# PMU.net
KiCad netlist of a schematic drawn in Altium Designer
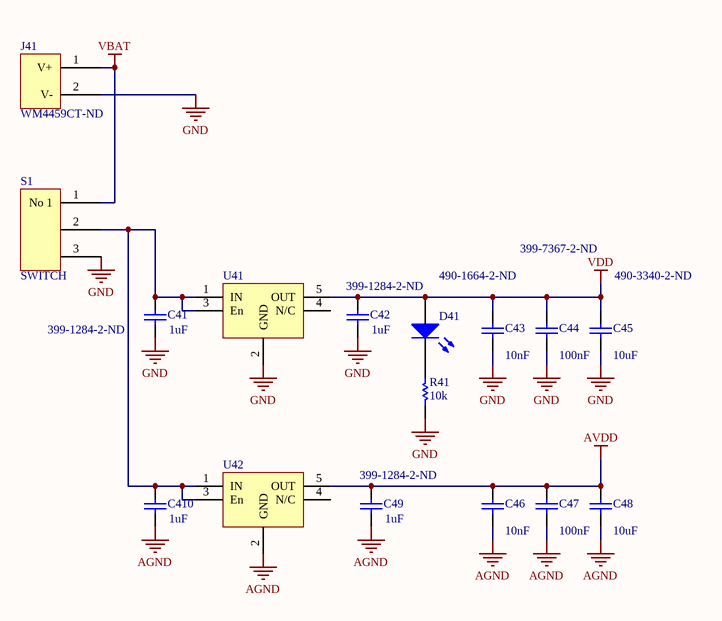
[diagram p0: PMU.SchDoc]

(export (version "E")
  (design (tool "Eeschema 10.0.6"))
  (components
    (comp (ref "C41")
      (value "1uF")
      (footprint "0402")
      (description "Capacitor (Semiconductor SIM Model)")
      (fields
        (field (name "SUPPLIER PART NUMBER 1") "399-1284-2-ND")
        (field (name "Comment") "Cap Semi")
        (field (name "PUBLISHER") "Altium Limited")
      )
      (libsource (lib "Miscellaneous Devices") (part "Cap Semi"))
    )
    (comp (ref "C42")
      (value "1uF")
      (footprint "0402")
      (description "Capacitor (Semiconductor SIM Model)")
      (fields
        (field (name "SUPPLIER PART NUMBER 1") "399-1284-2-ND")
        (field (name "Comment") "Cap Semi")
        (field (name "PUBLISHER") "Altium Limited")
      )
      (libsource (lib "Miscellaneous Devices") (part "Cap Semi"))
    )
    (comp (ref "C43")
      (value "10nF")
      (footprint "0402")
      (description "Capacitor (Semiconductor SIM Model)")
      (fields
        (field (name "SUPPLIER PART NUMBER 1") "490-1664-2-ND")
        (field (name "Comment") "Cap Semi")
        (field (name "PUBLISHER") "Altium Limited")
      )
      (libsource (lib "Miscellaneous Devices") (part "Cap Semi"))
    )
    (comp (ref "C44")
      (value "100nF")
      (footprint "0402")
      (description "Capacitor (Semiconductor SIM Model)")
      (fields
        (field (name "SUPPLIER PART NUMBER 1") "399-7367-2-ND")
        (field (name "Comment") "Cap Semi")
        (field (name "PUBLISHER") "Altium Limited")
      )
      (libsource (lib "Miscellaneous Devices") (part "Cap Semi"))
    )
    (comp (ref "C45")
      (value "10uF")
      (footprint "0402")
      (description "Capacitor (Semiconductor SIM Model)")
      (fields
        (field (name "SUPPLIER PART NUMBER 1") "490-3340-2-ND")
        (field (name "Comment") "Cap Semi")
        (field (name "PUBLISHER") "Altium Limited")
      )
      (libsource (lib "Miscellaneous Devices") (part "Cap Semi"))
    )
    (comp (ref "C46")
      (value "10nF")
      (footprint "0402")
      (description "Capacitor (Semiconductor SIM Model)")
      (fields (field (name "Comment") "Cap Semi") (field (name "PUBLISHER") "Altium Limited"))
      (libsource (lib "Miscellaneous Devices") (part "Cap Semi"))
    )
    (comp (ref "C47")
      (value "100nF")
      (footprint "0402")
      (description "Capacitor (Semiconductor SIM Model)")
      (fields (field (name "Comment") "Cap Semi") (field (name "PUBLISHER") "Altium Limited"))
      (libsource (lib "Miscellaneous Devices") (part "Cap Semi"))
    )
    (comp (ref "C48")
      (value "10uF")
      (footprint "0402")
      (description "Capacitor (Semiconductor SIM Model)")
      (fields (field (name "Comment") "Cap Semi") (field (name "PUBLISHER") "Altium Limited"))
      (libsource (lib "Miscellaneous Devices") (part "Cap Semi"))
    )
    (comp (ref "C49")
      (value "1uF")
      (footprint "0402")
      (description "Capacitor (Semiconductor SIM Model)")
      (fields
        (field (name "SUPPLIER PART NUMBER 1") "399-1284-2-ND")
        (field (name "Comment") "Cap Semi")
        (field (name "PUBLISHER") "Altium Limited")
      )
      (libsource (lib "Miscellaneous Devices") (part "Cap Semi"))
    )
    (comp (ref "C410")
      (value "1uF")
      (footprint "0402")
      (description "Capacitor (Semiconductor SIM Model)")
      (fields (field (name "Comment") "Cap Semi") (field (name "PUBLISHER") "Altium Limited"))
      (libsource (lib "Miscellaneous Devices") (part "Cap Semi"))
    )
    (comp (ref "D41")
      (value "Alim led verte")
      (footprint "0805 (2012 metric)")
      (description "LED 2X1.2MM 570NM GN WTR CLR SMD")
      (libsource (lib "Miscellaneous Devices") (part "LED3"))
    )
    (comp (ref "J41")
      (value "WM4459CT-ND")
      (footprint "WM4459CT-ND")
      (libsource (lib "WM4459CT-ND") (part "WM4459CT-ND"))
    )
    (comp (ref "R41")
      (value "10k")
      (footprint "0402")
      (description "Semiconductor Resistor")
      (fields (field (name "PUBLISHER") "Altium Limited"))
      (libsource (lib "Miscellaneous Devices") (part "Res Semi"))
    )
    (comp (ref "S1") (value "SWITCH") (footprint "CUS-12B") (libsource (lib "CUS-12B") (part "Component_1")))
    (comp (ref "U41")
      (value "Reg 3.3V")
      (footprint "TSOP-5ll")
      (description "IC REG LDO 3.3V 0.3A 5TSOP")
      (libsource (lib "EMG_library") (part "NCP603SN330T1G"))
    )
    (comp (ref "U42")
      (value "Reg 3.3V")
      (footprint "TSOP-5ll")
      (description "IC REG LDO 3.3V 0.3A 5TSOP")
      (libsource (lib "EMG_library") (part "NCP603SN330T1G"))
    )
  )
  (nets
    (net (code "1") (name "AGND") (class "Default")
      (node (ref "C410") (pin "1") (pinfunction "1_1") (pintype "passive"))
      (node (ref "C46") (pin "1") (pinfunction "1_1") (pintype "passive"))
      (node (ref "C47") (pin "1") (pinfunction "1_1") (pintype "passive"))
      (node (ref "C48") (pin "1") (pinfunction "1_1") (pintype "passive"))
      (node (ref "C49") (pin "1") (pinfunction "1_1") (pintype "passive"))
      (node (ref "U42") (pin "2") (pinfunction "GND_2") (pintype "power_in"))
    )
    (net (code "2") (name "AVDD") (class "Default")
      (node (ref "C46") (pin "2") (pinfunction "2_2") (pintype "passive"))
      (node (ref "C47") (pin "2") (pinfunction "2_2") (pintype "passive"))
      (node (ref "C48") (pin "2") (pinfunction "2_2") (pintype "passive"))
      (node (ref "C49") (pin "2") (pinfunction "2_2") (pintype "passive"))
      (node (ref "U42") (pin "5") (pinfunction "OUT_5") (pintype "power_in"))
    )
    (net (code "3") (name "GND") (class "Default")
      (node (ref "C41") (pin "1") (pinfunction "1_1") (pintype "passive"))
      (node (ref "C42") (pin "1") (pinfunction "1_1") (pintype "passive"))
      (node (ref "C43") (pin "1") (pinfunction "1_1") (pintype "passive"))
      (node (ref "C44") (pin "1") (pinfunction "1_1") (pintype "passive"))
      (node (ref "C45") (pin "1") (pinfunction "1_1") (pintype "passive"))
      (node (ref "J41") (pin "2") (pinfunction "V-_2") (pintype "passive"))
      (node (ref "R41") (pin "2") (pinfunction "2_2") (pintype "passive"))
      (node (ref "S1") (pin "3") (pinfunction "3_3") (pintype "passive"))
      (node (ref "U41") (pin "2") (pinfunction "GND_2") (pintype "power_in"))
    )
    (net (code "4") (name "Net-(D41-K)") (class "Default")
      (node (ref "D41") (pin "2") (pinfunction "K_2") (pintype "passive"))
      (node (ref "R41") (pin "1") (pinfunction "1_1") (pintype "passive"))
    )
    (net (code "5") (name "Net-(U41-En)") (class "Default")
      (node (ref "C41") (pin "2") (pinfunction "2_2") (pintype "passive"))
      (node (ref "C410") (pin "2") (pinfunction "2_2") (pintype "passive"))
      (node (ref "S1") (pin "2") (pinfunction "2_2") (pintype "passive"))
      (node (ref "U41") (pin "1") (pinfunction "IN_1") (pintype "power_in"))
      (node (ref "U41") (pin "3") (pinfunction "En_3") (pintype "power_in"))
      (node (ref "U42") (pin "1") (pinfunction "IN_1") (pintype "power_in"))
      (node (ref "U42") (pin "3") (pinfunction "En_3") (pintype "power_in"))
    )
    (net (code "6") (name "VBAT") (class "Default")
      (node (ref "J41") (pin "1") (pinfunction "V+_1") (pintype "passive"))
      (node (ref "S1") (pin "1") (pinfunction "No_1_1") (pintype "passive"))
    )
    (net (code "7") (name "VDD") (class "Default")
      (node (ref "C42") (pin "2") (pinfunction "2_2") (pintype "passive"))
      (node (ref "C43") (pin "2") (pinfunction "2_2") (pintype "passive"))
      (node (ref "C44") (pin "2") (pinfunction "2_2") (pintype "passive"))
      (node (ref "C45") (pin "2") (pinfunction "2_2") (pintype "passive"))
      (node (ref "D41") (pin "1") (pinfunction "A_1") (pintype "passive"))
      (node (ref "U41") (pin "5") (pinfunction "OUT_5") (pintype "power_in"))
    )
    (net (code "8") (name "unconnected-(U41-N{slash}C-Pad4)") (class "Default")
      (node (ref "U41") (pin "4") (pinfunction "N/C_4") (pintype "power_in"))
    )
    (net (code "9") (name "unconnected-(U42-N{slash}C-Pad4)") (class "Default")
      (node (ref "U42") (pin "4") (pinfunction "N/C_4") (pintype "power_in"))
    )
  )
)
